# MCU.net
KiCad netlist of a schematic drawn in Altium Designer
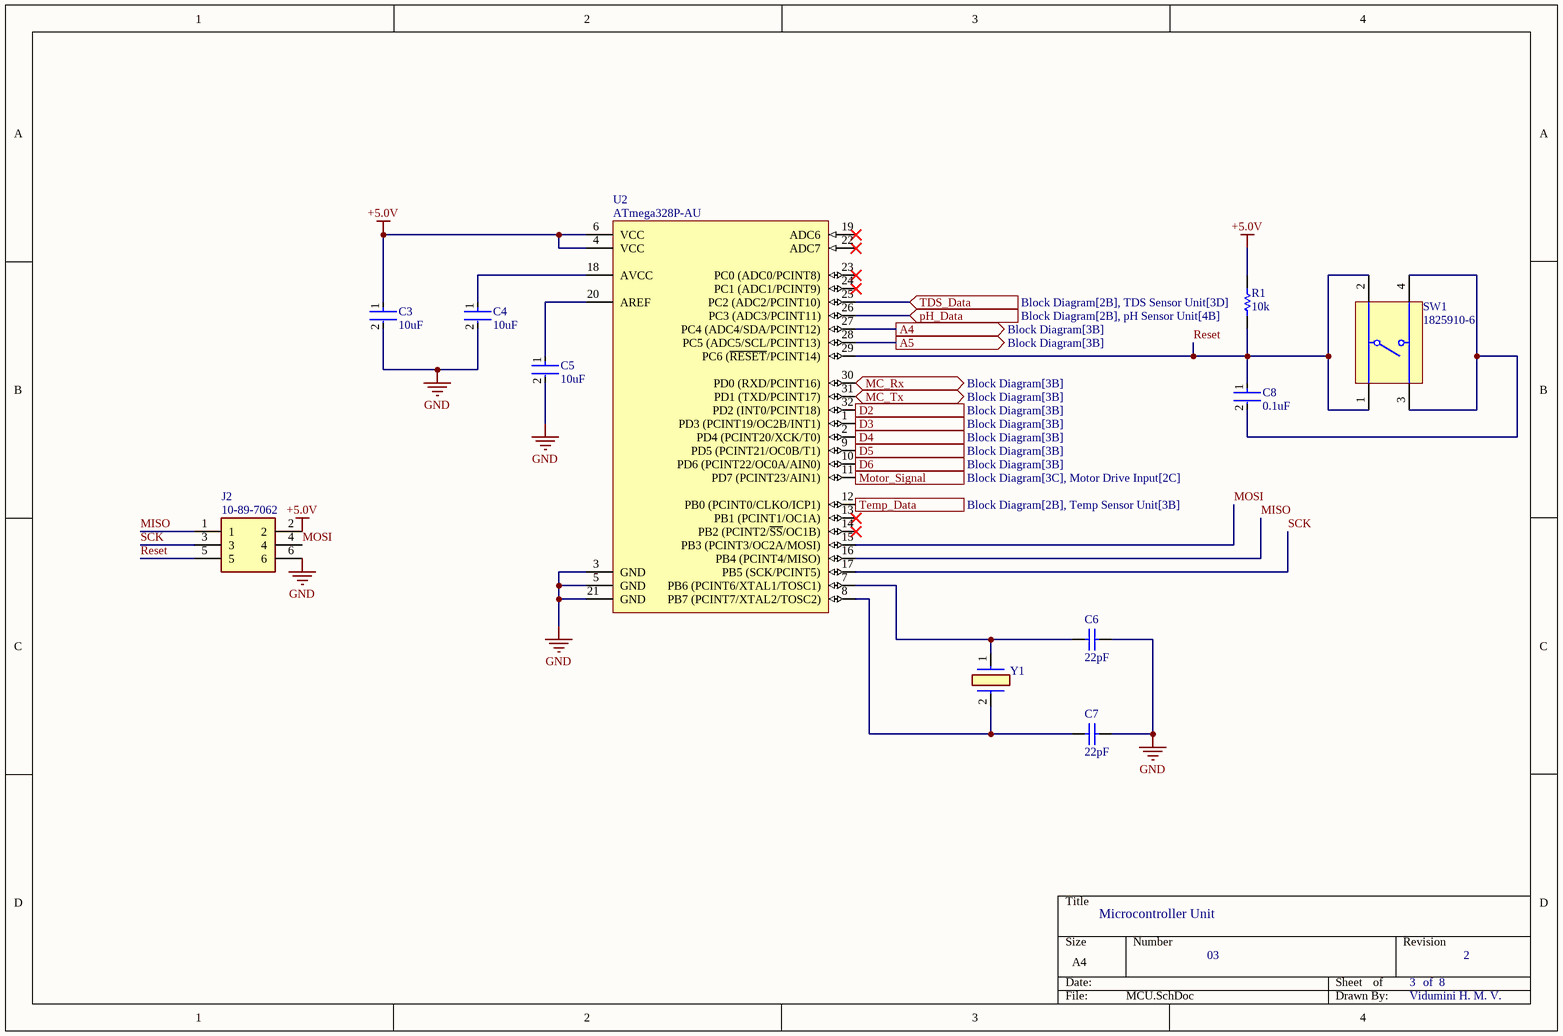
[diagram p0: MCU.SchDoc]

(export (version "E")
  (design (tool "Eeschema 10.0.6"))
  (components
    (comp (ref "C3")
      (value "10uF")
      (footprint "FP-1206-L_3_2_0_2-W_1_6_0-IPC_B")
      (description "General Purpose Ceramic Capacitor, 1206, 10uF, 10%, X5R, 15%, 16V")
      (fields (field (name "TOLERANCE") "10%") (field (name "VOLTAGE") "16V"))
      (libsource (lib "Altium Content Vault") (part "02cd4be3c70576c341d710602a673aa"))
    )
    (comp (ref "C4")
      (value "10uF")
      (footprint "FP-1206-L_3_2_0_2-W_1_6_0-IPC_B")
      (description "General Purpose Ceramic Capacitor, 1206, 10uF, 10%, X5R, 15%, 16V")
      (fields (field (name "TOLERANCE") "10%") (field (name "VOLTAGE") "16V"))
      (libsource (lib "Altium Content Vault") (part "02cd4be3c70576c341d710602a673aa"))
    )
    (comp (ref "C5")
      (value "10uF")
      (footprint "FP-1206-L_3_2_0_2-W_1_6_0-IPC_B")
      (description "General Purpose Ceramic Capacitor, 1206, 10uF, 10%, X5R, 15%, 16V")
      (fields (field (name "TOLERANCE") "10%") (field (name "VOLTAGE") "16V"))
      (libsource (lib "Altium Content Vault") (part "02cd4be3c70576c341d710602a673aa"))
    )
    (comp (ref "C6")
      (value "22pF")
      (footprint "CAPC2013X115X51NL20T26")
      (fields
        (field (name "MANUFACTURER") "AVX Interconnect / Elco")
        (field (name "PART NUMBER") "08052U220GAT2A")
      )
      (libsource (lib "Altium Content Vault") (part "CAP"))
    )
    (comp (ref "C7")
      (value "22pF")
      (footprint "CAPC2013X115X51NL20T26")
      (fields
        (field (name "MANUFACTURER") "AVX Interconnect / Elco")
        (field (name "PART NUMBER") "08052U220GAT2A")
      )
      (libsource (lib "Altium Content Vault") (part "CAP"))
    )
    (comp (ref "C8")
      (value "0.1uF")
      (footprint "FP-1206-L_3_2_0_2-W_1_6_0-IPC_B")
      (description "General Purpose Ceramic Capacitor, 1206, 100nF, 10%, X7R, 15%, 10V")
      (fields (field (name "TOLERANCE") "10%"))
      (libsource (lib "Altium Content Vault") (part "02cd4be3c70576c341d710602a673aa"))
    )
    (comp (ref "J2")
      (value "10-89-7062")
      (footprint "SamacSys:HDRV6W87P254_2X3_775X508X864P")
      (description "Connector")
      (fields (field (name "MOUSER PART NUMBER") "538-10-89-7062"))
      (libsource (lib "*") (part "10-89-7062"))
    )
    (comp (ref "R1")
      (value "10k")
      (footprint "RESC3116X65X40ML10T20")
      (description "Chip Resistor, 10 KOhm, +/- 1%, 0.25 W, -55 to 155 degC, 1206 (3216 Metric), RoHS, Tape and Reel")
      (fields (field (name "TOLERANCE") "1%") (field (name "MANUFACTURER") "Yageo"))
      (libsource (lib "Altium Content Vault") (part "RES-2"))
    )
    (comp (ref "SW1")
      (value "1825910-6")
      (footprint "TECO-1825910-6_V")
      (description "Tact Switch, SPST-NO, 0.05 A, -35 to 85 degC, 4-Pin THD, RoHS, Bulk")
      (fields (field (name "MANUFACTURER") "TE Connectivity"))
      (libsource (lib "Altium Content Vault") (part "SW-SPST-4_A"))
    )
    (comp (ref "U2")
      (value "ATmega328P-AU")
      (footprint "32A_M")
      (libsource (lib "Altium Content Vault") (part "MC-8B-ATM48-SQ32"))
    )
    (comp (ref "Y1")
      (value "ECS-160-20-3X-TR")
      (footprint "SamacSys:ECS160203XTR")
      (description "Crystal or Oscillator")
      (fields (field (name "MOUSER PART NUMBER") "520-160-20-3XT"))
      (libsource (lib "*") (part "ECS-160-20-3X-TR"))
    )
  )
  (nets
    (net (code "1") (name "+5.0V") (class "Default")
      (node (ref "C3") (pin "1") (pinfunction "1_1") (pintype "passive"))
      (node (ref "J2") (pin "2") (pinfunction "2_2") (pintype "passive"))
      (node (ref "R1") (pin "2") (pinfunction "2_2") (pintype "passive"))
      (node (ref "U2") (pin "4") (pinfunction "VCC_4") (pintype "power_in"))
      (node (ref "U2") (pin "6") (pinfunction "VCC_6") (pintype "power_in"))
    )
    (net (code "2") (name "/A4") (class "Default")
      (node (ref "U2") (pin "27") (pinfunction "PC4_(ADC4/SDA/PCINT12)_27") (pintype "bidirectional"))
    )
    (net (code "3") (name "/A5") (class "Default")
      (node (ref "U2") (pin "28") (pinfunction "PC5_(ADC5/SCL/PCINT13)_28") (pintype "bidirectional"))
    )
    (net (code "4") (name "/D2") (class "Default")
      (node (ref "U2") (pin "32") (pinfunction "PD2_(INT0/PCINT18)_32") (pintype "bidirectional"))
    )
    (net (code "5") (name "/D3") (class "Default")
      (node (ref "U2") (pin "1") (pinfunction "PD3_(PCINT19/OC2B/INT1)_1") (pintype "bidirectional"))
    )
    (net (code "6") (name "/D4") (class "Default")
      (node (ref "U2") (pin "2") (pinfunction "PD4_(PCINT20/XCK/T0)_2") (pintype "bidirectional"))
    )
    (net (code "7") (name "/D5") (class "Default")
      (node (ref "U2") (pin "9") (pinfunction "PD5_(PCINT21/OC0B/T1)_9") (pintype "bidirectional"))
    )
    (net (code "8") (name "/D6") (class "Default")
      (node (ref "U2") (pin "10") (pinfunction "PD6_(PCINT22/OC0A/AIN0)_10") (pintype "bidirectional"))
    )
    (net (code "9") (name "/MC_Rx") (class "Default")
      (node (ref "U2") (pin "30") (pinfunction "PD0_(RXD/PCINT16)_30") (pintype "bidirectional"))
    )
    (net (code "10") (name "/MC_Tx") (class "Default")
      (node (ref "U2") (pin "31") (pinfunction "PD1_(TXD/PCINT17)_31") (pintype "bidirectional"))
    )
    (net (code "11") (name "/MISO") (class "Default")
      (node (ref "J2") (pin "1") (pinfunction "1_1") (pintype "passive"))
      (node (ref "U2") (pin "16") (pinfunction "PB4_(PCINT4/MISO)_16") (pintype "bidirectional"))
    )
    (net (code "12") (name "/MOSI") (class "Default")
      (node (ref "J2") (pin "4") (pinfunction "4_4") (pintype "passive"))
      (node (ref "U2") (pin "15") (pinfunction "PB3_(PCINT3/OC2A/MOSI)_15") (pintype "bidirectional"))
    )
    (net (code "13") (name "/Motor_Signal") (class "Default")
      (node (ref "U2") (pin "11") (pinfunction "PD7_(PCINT23/AIN1)_11") (pintype "bidirectional"))
    )
    (net (code "14") (name "/Reset") (class "Default")
      (node (ref "C8") (pin "1") (pinfunction "1_1") (pintype "passive"))
      (node (ref "J2") (pin "5") (pinfunction "5_5") (pintype "passive"))
      (node (ref "R1") (pin "1") (pinfunction "1_1") (pintype "passive"))
      (node (ref "SW1") (pin "1") (pinfunction "1_1") (pintype "passive"))
      (node (ref "SW1") (pin "2") (pinfunction "2_2") (pintype "passive"))
      (node (ref "U2") (pin "29") (pinfunction "PC6_(~{RESET}/PCINT14)_29") (pintype "bidirectional"))
    )
    (net (code "15") (name "/SCK") (class "Default")
      (node (ref "J2") (pin "3") (pinfunction "3_3") (pintype "passive"))
      (node (ref "U2") (pin "17") (pinfunction "PB5_(SCK/PCINT5)_17") (pintype "bidirectional"))
    )
    (net (code "16") (name "/TDS_Data") (class "Default")
      (node (ref "U2") (pin "25") (pinfunction "PC2_(ADC2/PCINT10)_25") (pintype "bidirectional"))
    )
    (net (code "17") (name "/Temp_Data") (class "Default")
      (node (ref "U2") (pin "12") (pinfunction "PB0_(PCINT0/CLKO/ICP1)_12") (pintype "bidirectional"))
    )
    (net (code "18") (name "/pH_Data") (class "Default")
      (node (ref "U2") (pin "26") (pinfunction "PC3_(ADC3/PCINT11)_26") (pintype "bidirectional"))
    )
    (net (code "19") (name "GND") (class "Default")
      (node (ref "C3") (pin "2") (pinfunction "2_2") (pintype "passive"))
      (node (ref "C4") (pin "2") (pinfunction "2_2") (pintype "passive"))
      (node (ref "C5") (pin "2") (pinfunction "2_2") (pintype "passive"))
      (node (ref "C6") (pin "2") (pinfunction "2_2") (pintype "passive"))
      (node (ref "C7") (pin "2") (pinfunction "2_2") (pintype "passive"))
      (node (ref "J2") (pin "6") (pinfunction "6_6") (pintype "passive"))
      (node (ref "U2") (pin "21") (pinfunction "GND_21") (pintype "power_in"))
      (node (ref "U2") (pin "3") (pinfunction "GND_3") (pintype "power_in"))
      (node (ref "U2") (pin "5") (pinfunction "GND_5") (pintype "power_in"))
    )
    (net (code "20") (name "Net-(C8-Pad2)") (class "Default")
      (node (ref "C8") (pin "2") (pinfunction "2_2") (pintype "passive"))
      (node (ref "SW1") (pin "3") (pinfunction "3_3") (pintype "passive"))
      (node (ref "SW1") (pin "4") (pinfunction "4_4") (pintype "passive"))
    )
    (net (code "21") (name "Net-(U2-AREF)") (class "Default")
      (node (ref "C5") (pin "1") (pinfunction "1_1") (pintype "passive"))
      (node (ref "U2") (pin "20") (pinfunction "AREF_20") (pintype "passive"))
    )
    (net (code "22") (name "Net-(U2-AVCC)") (class "Default")
      (node (ref "C4") (pin "1") (pinfunction "1_1") (pintype "passive"))
      (node (ref "U2") (pin "18") (pinfunction "AVCC_18") (pintype "power_in"))
    )
    (net (code "23") (name "Net-(U2-PB6_(PCINT6{slash}XTAL1{slash}TOSC1))") (class "Default")
      (node (ref "C6") (pin "1") (pinfunction "1_1") (pintype "passive"))
      (node (ref "U2") (pin "7") (pinfunction "PB6_(PCINT6/XTAL1/TOSC1)_7") (pintype "bidirectional"))
      (node (ref "Y1") (pin "1") (pinfunction "X1_1") (pintype "passive"))
    )
    (net (code "24") (name "Net-(U2-PB7_(PCINT7{slash}XTAL2{slash}TOSC2))") (class "Default")
      (node (ref "C7") (pin "1") (pinfunction "1_1") (pintype "passive"))
      (node (ref "U2") (pin "8") (pinfunction "PB7_(PCINT7/XTAL2/TOSC2)_8") (pintype "bidirectional"))
      (node (ref "Y1") (pin "2") (pinfunction "X2_2") (pintype "passive"))
    )
    (net (code "25") (name "unconnected-(U2-ADC6-Pad19)") (class "Default")
      (node (ref "U2") (pin "19") (pinfunction "ADC6_19") (pintype "input+no_connect"))
    )
    (net (code "26") (name "unconnected-(U2-ADC7-Pad22)") (class "Default")
      (node (ref "U2") (pin "22") (pinfunction "ADC7_22") (pintype "input+no_connect"))
    )
    (net (code "27") (name "unconnected-(U2-PB1_(PCINT1{slash}OC1A)-Pad13)") (class "Default")
      (node (ref "U2") (pin "13") (pinfunction "PB1_(PCINT1/OC1A)_13") (pintype "bidirectional+no_connect"))
    )
    (net (code "28") (name "unconnected-(U2-PB2_(PCINT2{slash}~{SS}{slash}OC1B)-Pad14)") (class "Default")
      (node (ref "U2") (pin "14") (pinfunction "PB2_(PCINT2/~{SS}/OC1B)_14") (pintype "bidirectional+no_connect"))
    )
    (net (code "29") (name "unconnected-(U2-PC0_(ADC0{slash}PCINT8)-Pad23)") (class "Default")
      (node (ref "U2") (pin "23") (pinfunction "PC0_(ADC0/PCINT8)_23") (pintype "bidirectional+no_connect"))
    )
    (net (code "30") (name "unconnected-(U2-PC1_(ADC1{slash}PCINT9)-Pad24)") (class "Default")
      (node (ref "U2") (pin "24") (pinfunction "PC1_(ADC1/PCINT9)_24") (pintype "bidirectional+no_connect"))
    )
  )
)
